# Level_Shifter.net
KiCad netlist of a schematic drawn in Altium Designer
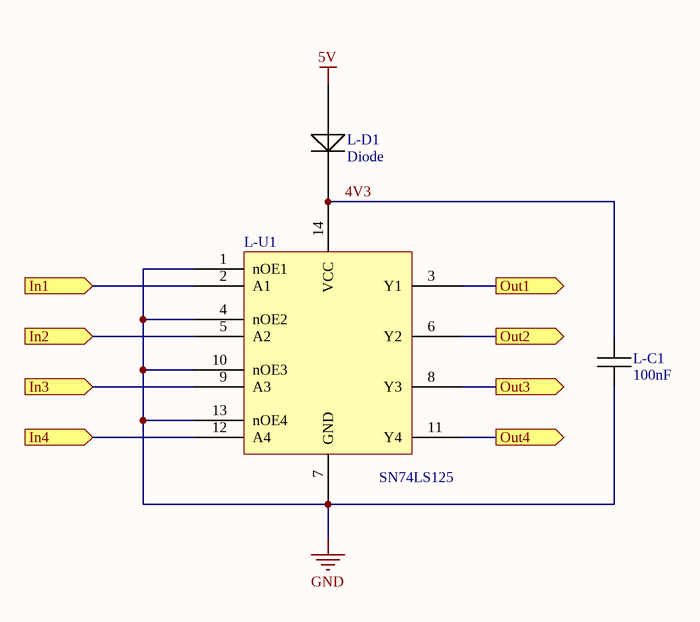
[diagram p0: Level Shifter.SchDoc]

(export (version "E")
  (design (tool "Eeschema 10.0.6"))
  (components
    (comp (ref "L-C1")
      (value "100nF")
      (footprint "C 0805 / 2012")
      (libsource (lib "Standard") (part "Capacitor"))
    )
    (comp (ref "L-D1") (value "Diode") (footprint "DO-41") (libsource (lib "Standard") (part "Diode")))
    (comp (ref "L-U1")
      (value "SN74LS125")
      (footprint "DIP-14")
      (description "Quad 3-State Buffers")
      (libsource (lib "ICs") (part "74xx125"))
    )
  )
  (nets
    (net (code "1") (name "/4V3") (class "Default")
      (node (ref "L-C1") (pin "1") (pinfunction "1_1") (pintype "passive"))
      (node (ref "L-D1") (pin "1") (pinfunction "1_1") (pintype "passive"))
      (node (ref "L-U1") (pin "14") (pinfunction "VCC_14") (pintype "passive"))
    )
    (net (code "2") (name "/In1") (class "Default")
      (node (ref "L-U1") (pin "2") (pinfunction "A1_2") (pintype "passive"))
    )
    (net (code "3") (name "/In2") (class "Default")
      (node (ref "L-U1") (pin "5") (pinfunction "A2_5") (pintype "passive"))
    )
    (net (code "4") (name "/In3") (class "Default")
      (node (ref "L-U1") (pin "9") (pinfunction "A3_9") (pintype "passive"))
    )
    (net (code "5") (name "/In4") (class "Default")
      (node (ref "L-U1") (pin "12") (pinfunction "A4_12") (pintype "passive"))
    )
    (net (code "6") (name "/Out1") (class "Default")
      (node (ref "L-U1") (pin "3") (pinfunction "Y1_3") (pintype "passive"))
    )
    (net (code "7") (name "/Out2") (class "Default")
      (node (ref "L-U1") (pin "6") (pinfunction "Y2_6") (pintype "passive"))
    )
    (net (code "8") (name "/Out3") (class "Default")
      (node (ref "L-U1") (pin "8") (pinfunction "Y3_8") (pintype "passive"))
    )
    (net (code "9") (name "/Out4") (class "Default")
      (node (ref "L-U1") (pin "11") (pinfunction "Y4_11") (pintype "passive"))
    )
    (net (code "10") (name "5V") (class "Default")
      (node (ref "L-D1") (pin "2") (pinfunction "2_2") (pintype "passive"))
    )
    (net (code "11") (name "GND") (class "Default")
      (node (ref "L-C1") (pin "2") (pinfunction "1_2") (pintype "passive"))
      (node (ref "L-U1") (pin "1") (pinfunction "nOE1_1") (pintype "passive"))
      (node (ref "L-U1") (pin "10") (pinfunction "nOE3_10") (pintype "passive"))
      (node (ref "L-U1") (pin "13") (pinfunction "nOE4_13") (pintype "passive"))
      (node (ref "L-U1") (pin "4") (pinfunction "nOE2_4") (pintype "passive"))
      (node (ref "L-U1") (pin "7") (pinfunction "GND_7") (pintype "passive"))
    )
  )
)
